# 8_-DAC_and_MIC.net
KiCad netlist of a schematic drawn in Altium Designer
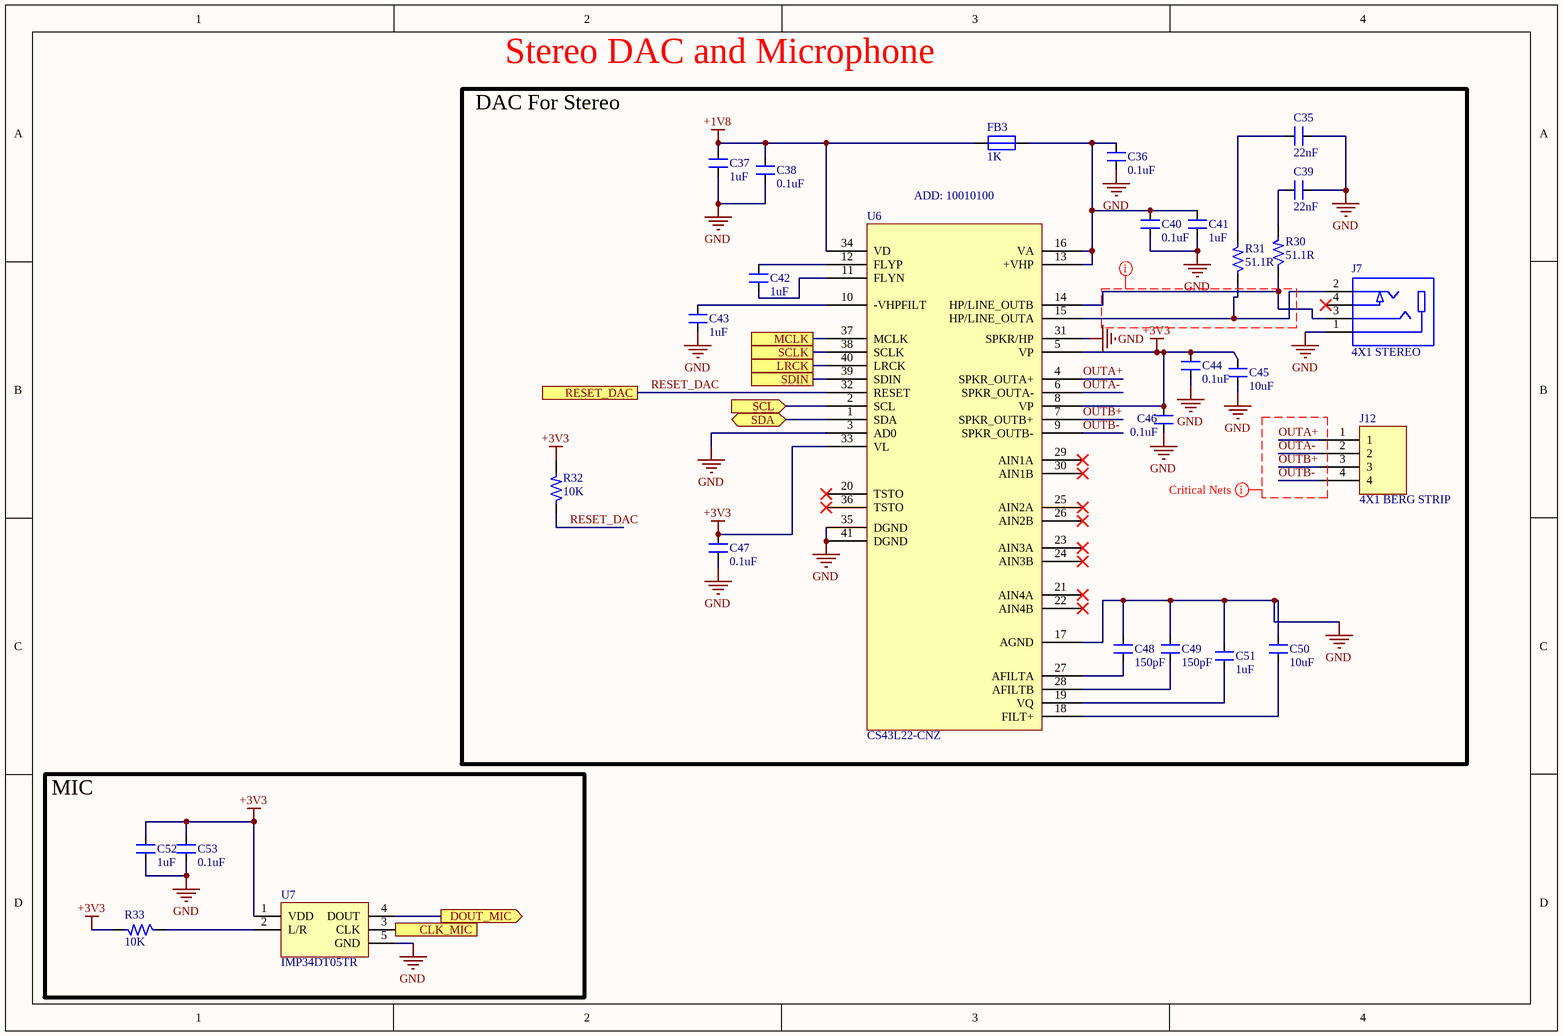
[diagram p0: [8]-DAC and MIC.SchDoc]

(export (version "E")
  (design (tool "Eeschema 10.0.6"))
  (components
    (comp (ref "C35")
      (value "22nF")
      (footprint "CAP_0805")
      (description "0.022µF ±10% 50V Ceramic Capacitor X7R 0805 (2012 Metric)")
      (fields
        (field (name "MANUFACTURER") "Samsung Electro-Mechanics")
        (field (name "MANUFACTURER PART NUMBER") "CL21B223KBANNNC")
      )
      (libsource (lib "ESTEEMPCBLIB") (part "CAP_22nF-50V-10%-0805"))
    )
    (comp (ref "C36")
      (value "0.1uF")
      (footprint "CAP_0805")
      (description "0.1µF ±10% 50V Ceramic Capacitor X7R 0805 (2012 Metric)")
      (fields
        (field (name "MANUFACTURER") "Samsung")
        (field (name "MANUFACTURER PART NUMBER") "CL21B104KBCNNNC")
      )
      (libsource (lib "ESTEEMPCBLIB") (part "CAP_0.1uF-50V-10%-0805"))
    )
    (comp (ref "C37")
      (value "1uF")
      (footprint "CAP_0805")
      (description "1µF ±5% 50V Ceramic Capacitor X7R 0805 (2012 Metric)")
      (fields
        (field (name "MANUFACTURER") "Samsung")
        (field (name "MANUFACTURER PART NUMBER") "CC0805JKX7R9BB105")
      )
      (libsource (lib "ESTEEMPCBLIB") (part "CAP_1uF-50V-5%-0805"))
    )
    (comp (ref "C38")
      (value "0.1uF")
      (footprint "CAP_0805")
      (description "0.1µF ±10% 50V Ceramic Capacitor X7R 0805 (2012 Metric)")
      (fields
        (field (name "MANUFACTURER") "Samsung")
        (field (name "MANUFACTURER PART NUMBER") "CL21B104KBCNNNC")
      )
      (libsource (lib "ESTEEMPCBLIB") (part "CAP_0.1uF-50V-10%-0805"))
    )
    (comp (ref "C39")
      (value "22nF")
      (footprint "CAP_0805")
      (description "0.022µF ±10% 50V Ceramic Capacitor X7R 0805 (2012 Metric)")
      (fields
        (field (name "MANUFACTURER") "Samsung Electro-Mechanics")
        (field (name "MANUFACTURER PART NUMBER") "CL21B223KBANNNC")
      )
      (libsource (lib "ESTEEMPCBLIB") (part "CAP_22nF-50V-10%-0805"))
    )
    (comp (ref "C40")
      (value "0.1uF")
      (footprint "CAP_0805")
      (description "0.1µF ±10% 50V Ceramic Capacitor X7R 0805 (2012 Metric)")
      (fields
        (field (name "MANUFACTURER") "Samsung")
        (field (name "MANUFACTURER PART NUMBER") "CL21B104KBCNNNC")
      )
      (libsource (lib "ESTEEMPCBLIB") (part "CAP_0.1uF-50V-10%-0805"))
    )
    (comp (ref "C41")
      (value "1uF")
      (footprint "CAP_0805")
      (description "1µF ±5% 50V Ceramic Capacitor X7R 0805 (2012 Metric)")
      (fields
        (field (name "MANUFACTURER") "Samsung")
        (field (name "MANUFACTURER PART NUMBER") "CC0805JKX7R9BB105")
      )
      (libsource (lib "ESTEEMPCBLIB") (part "CAP_1uF-50V-5%-0805"))
    )
    (comp (ref "C42")
      (value "1uF")
      (footprint "CAP_0805")
      (description "1µF ±5% 50V Ceramic Capacitor X7R 0805 (2012 Metric)")
      (fields
        (field (name "MANUFACTURER") "Samsung")
        (field (name "MANUFACTURER PART NUMBER") "CC0805JKX7R9BB105")
      )
      (libsource (lib "ESTEEMPCBLIB") (part "CAP_1uF-50V-5%-0805"))
    )
    (comp (ref "C43")
      (value "1uF")
      (footprint "CAP_0805")
      (description "1µF ±5% 50V Ceramic Capacitor X7R 0805 (2012 Metric)")
      (fields
        (field (name "MANUFACTURER") "Samsung")
        (field (name "MANUFACTURER PART NUMBER") "CC0805JKX7R9BB105")
      )
      (libsource (lib "ESTEEMPCBLIB") (part "CAP_1uF-50V-5%-0805"))
    )
    (comp (ref "C44")
      (value "0.1uF")
      (footprint "CAP_0805")
      (description "0.1µF ±10% 50V Ceramic Capacitor X7R 0805 (2012 Metric)")
      (fields
        (field (name "MANUFACTURER") "Samsung")
        (field (name "MANUFACTURER PART NUMBER") "CL21B104KBCNNNC")
      )
      (libsource (lib "ESTEEMPCBLIB") (part "CAP_0.1uF-50V-10%-0805"))
    )
    (comp (ref "C45")
      (value "10uF")
      (footprint "CAP_1206")
      (description "10µF ±10% 50V Ceramic Capacitor X7R 1206 (3216 Metric)")
      (fields
        (field (name "MANUFACTURER") "KEMET")
        (field (name "MANUFACTURER PART NUMBER") "CL31B106KBHNNNE")
      )
      (libsource (lib "ESTEEMPCBLIB") (part "CAP_10uF-50V-10%-1206"))
    )
    (comp (ref "C46")
      (value "0.1uF")
      (footprint "CAP_0805")
      (description "0.1µF ±10% 50V Ceramic Capacitor X7R 0805 (2012 Metric)")
      (fields
        (field (name "MANUFACTURER") "Samsung")
        (field (name "MANUFACTURER PART NUMBER") "CL21B104KBCNNNC")
      )
      (libsource (lib "ESTEEMPCBLIB") (part "CAP_0.1uF-50V-10%-0805"))
    )
    (comp (ref "C47")
      (value "0.1uF")
      (footprint "CAP_0805")
      (description "0.1µF ±10% 50V Ceramic Capacitor X7R 0805 (2012 Metric)")
      (fields
        (field (name "MANUFACTURER") "Samsung")
        (field (name "MANUFACTURER PART NUMBER") "CL21B104KBCNNNC")
      )
      (libsource (lib "ESTEEMPCBLIB") (part "CAP_0.1uF-50V-10%-0805"))
    )
    (comp (ref "C48")
      (value "150pF")
      (footprint "CAP_0805")
      (description "150pF ±10% 50V Ceramic Capacitor C0G, NP0 0805 (2012 Metric)")
      (fields
        (field (name "MANUFACTURER") "AVX Corporation")
        (field (name "MANUFACTURER PART NUMBER") "08055A151KAT2A")
      )
      (libsource (lib "ESTEEMPCBLIB") (part "CAP_150pF-50V-10%-0805"))
    )
    (comp (ref "C49")
      (value "150pF")
      (footprint "CAP_0805")
      (description "150pF ±10% 50V Ceramic Capacitor C0G, NP0 0805 (2012 Metric)")
      (fields
        (field (name "MANUFACTURER") "AVX Corporation")
        (field (name "MANUFACTURER PART NUMBER") "08055A151KAT2A")
      )
      (libsource (lib "ESTEEMPCBLIB") (part "CAP_150pF-50V-10%-0805"))
    )
    (comp (ref "C50")
      (value "10uF")
      (footprint "CAP_1206")
      (description "10µF ±10% 50V Ceramic Capacitor X7R 1206 (3216 Metric)")
      (fields
        (field (name "MANUFACTURER") "KEMET")
        (field (name "MANUFACTURER PART NUMBER") "CL31B106KBHNNNE")
      )
      (libsource (lib "ESTEEMPCBLIB") (part "CAP_10uF-50V-10%-1206"))
    )
    (comp (ref "C51")
      (value "1uF")
      (footprint "CAP_0805")
      (description "1µF ±5% 50V Ceramic Capacitor X7R 0805 (2012 Metric)")
      (fields
        (field (name "MANUFACTURER") "Samsung")
        (field (name "MANUFACTURER PART NUMBER") "CC0805JKX7R9BB105")
      )
      (libsource (lib "ESTEEMPCBLIB") (part "CAP_1uF-50V-5%-0805"))
    )
    (comp (ref "C52")
      (value "1uF")
      (footprint "CAP_0805")
      (description "1µF ±5% 50V Ceramic Capacitor X7R 0805 (2012 Metric)")
      (fields
        (field (name "MANUFACTURER") "Samsung")
        (field (name "MANUFACTURER PART NUMBER") "CC0805JKX7R9BB105")
      )
      (libsource (lib "ESTEEMPCBLIB") (part "CAP_1uF-50V-5%-0805"))
    )
    (comp (ref "C53")
      (value "0.1uF")
      (footprint "CAP_0805")
      (description "0.1µF ±10% 50V Ceramic Capacitor X7R 0805 (2012 Metric)")
      (fields
        (field (name "MANUFACTURER") "Samsung")
        (field (name "MANUFACTURER PART NUMBER") "CL21B104KBCNNNC")
      )
      (libsource (lib "ESTEEMPCBLIB") (part "CAP_0.1uF-50V-10%-0805"))
    )
    (comp (ref "FB3")
      (value "1K")
      (footprint "IND_0805")
      (description "1 kOhms @ 100MHz 1 Power Line Ferrite Bead 0805 (2012 Metric) 1.6A")
      (fields
        (field (name "MANUFACTURER") "Laird")
        (field (name "MANUFACTURER PART NUMBER") "BLM21SP102SH1D")
      )
      (libsource (lib "ESTEEMPCBLIB") (part "FB_1K-100MHZ-1.6A-0805"))
    )
    (comp (ref "J7")
      (value "4X1 STEREO")
      (footprint "CON_SJ-2504A-SMT-TR_SMD")
      (fields
        (field (name "MANUFACTURER") "CUI Devices")
        (field (name "MANUFACTURER PART NUMBER") "SJ-2504A-SMT-TR")
      )
      (libsource (lib "ESTEEMPCBLIB") (part "CON-PLG-STEREO_4X1-100-RA-SMD"))
    )
    (comp (ref "J12")
      (value "4X1 BERG STRIP")
      (footprint "CON4_100_40D72_TH_ST_MALE")
      (description "4 Pins, 1 Row 2.54mm Pitch, Straight bergstrip, Male")
      (fields (field (name "MANUFACTURER") "NA"))
      (libsource (lib "ESTEEMPCBLIB") (part "CON-BS-PLG_4X1-100-ST-TH"))
    )
    (comp (ref "R30")
      (value "51.1R")
      (footprint "RES_0603")
      (description "51.1 Ohms ±1% 0.1W, 1/10W Chip Resistor 0603 (1608 Metric) Thick Film")
      (fields
        (field (name "MANUFACTURER") "Vishay Dale")
        (field (name "MANUFACTURER PART NUMBER") "CRCW060351R1FKEAC")
      )
      (libsource (lib "ESTEEMPCBLIB") (part "RES_51.1R-0.1W-1%-0603"))
    )
    (comp (ref "R31")
      (value "51.1R")
      (footprint "RES_0603")
      (description "51.1 Ohms ±1% 0.1W, 1/10W Chip Resistor 0603 (1608 Metric) Thick Film")
      (fields
        (field (name "MANUFACTURER") "Vishay Dale")
        (field (name "MANUFACTURER PART NUMBER") "CRCW060351R1FKEAC")
      )
      (libsource (lib "ESTEEMPCBLIB") (part "RES_51.1R-0.1W-1%-0603"))
    )
    (comp (ref "R32")
      (value "10K")
      (footprint "RES_0603")
      (description "10 kOhms ±1% 0.1W, 1/10W Chip Resistor 0603 (1608 Metric) Automotive AEC-Q200 Thick Film")
      (fields (field (name "MANUFACTURER") "Walsin") (field (name "MANUFACTURER PART NUMBER") "WR06X1002FTL"))
      (libsource (lib "ESTEEMPCBLIB") (part "RES_10K-0.1W-1%-0603"))
    )
    (comp (ref "R33")
      (value "10K")
      (footprint "RES_0603")
      (description "10 kOhms ±1% 0.1W, 1/10W Chip Resistor 0603 (1608 Metric) Automotive AEC-Q200 Thick Film")
      (fields (field (name "MANUFACTURER") "Walsin") (field (name "MANUFACTURER PART NUMBER") "WR06X1002FTL"))
      (libsource (lib "ESTEEMPCBLIB") (part "RES_10K-0.1W-1%-0603"))
    )
    (comp (ref "U6")
      (value "CS43L22-CNZ")
      (footprint "QFN40_19_284_33X9_SMD")
      (description "Audio D/A Converter ICs Low Power Stereo DAC w/ClassD Spkr Driver")
      (fields (field (name "MANUFACTURER") "Cirrus Logic"))
      (libsource (lib "ESTEEMPCBLIB") (part "IC_CS43L22"))
    )
    (comp (ref "U7")
      (value "IMP34DT05TR")
      (footprint "HCLGA-4_53_137_15X37_SMD")
      (description "MEMS Microphones AUTO & INDUSTRIAL SENSORS")
      (fields (field (name "MANUFACTURER") "STMicroelectronics"))
      (libsource (lib "ESTEEMPCBLIB") (part "IC_IMP34DT05TR"))
    )
  )
  (nets
    (net (code "1") (name "+1V8") (class "Default")
      (node (ref "C37") (pin "2") (pinfunction "2_2") (pintype "passive"))
      (node (ref "C38") (pin "2") (pinfunction "2_2") (pintype "passive"))
      (node (ref "FB3") (pin "1") (pinfunction "1_1") (pintype "passive"))
      (node (ref "U6") (pin "34") (pinfunction "VD_34") (pintype "passive"))
    )
    (net (code "2") (name "+3V3") (class "Default")
      (node (ref "C44") (pin "2") (pinfunction "2_2") (pintype "passive"))
      (node (ref "C45") (pin "2") (pinfunction "2_2") (pintype "passive"))
      (node (ref "C46") (pin "2") (pinfunction "2_2") (pintype "passive"))
      (node (ref "C47") (pin "2") (pinfunction "2_2") (pintype "passive"))
      (node (ref "C52") (pin "2") (pinfunction "2_2") (pintype "passive"))
      (node (ref "C53") (pin "2") (pinfunction "2_2") (pintype "passive"))
      (node (ref "R32") (pin "2") (pinfunction "2_2") (pintype "passive"))
      (node (ref "R33") (pin "2") (pinfunction "2_2") (pintype "passive"))
      (node (ref "U6") (pin "33") (pinfunction "VL_33") (pintype "passive"))
      (node (ref "U6") (pin "5") (pinfunction "VP_5") (pintype "passive"))
      (node (ref "U6") (pin "8") (pinfunction "VP_8") (pintype "passive"))
      (node (ref "U7") (pin "1") (pinfunction "VDD_1") (pintype "passive"))
    )
    (net (code "3") (name "/CLK_MIC") (class "Default")
      (node (ref "U7") (pin "3") (pinfunction "CLK_3") (pintype "passive"))
    )
    (net (code "4") (name "/DOUT_MIC") (class "Default")
      (node (ref "U7") (pin "4") (pinfunction "DOUT_4") (pintype "passive"))
    )
    (net (code "5") (name "/LRCK") (class "Default")
      (node (ref "U6") (pin "40") (pinfunction "LRCK_40") (pintype "passive"))
    )
    (net (code "6") (name "/MCLK") (class "Default")
      (node (ref "U6") (pin "37") (pinfunction "MCLK_37") (pintype "passive"))
    )
    (net (code "7") (name "/OUTA+") (class "Default")
      (node (ref "J12") (pin "1") (pinfunction "1_1") (pintype "passive"))
      (node (ref "U6") (pin "4") (pinfunction "SPKR_OUTA+_4") (pintype "passive"))
    )
    (net (code "8") (name "/OUTA-") (class "Default")
      (node (ref "J12") (pin "2") (pinfunction "2_2") (pintype "passive"))
      (node (ref "U6") (pin "6") (pinfunction "SPKR_OUTA-_6") (pintype "passive"))
    )
    (net (code "9") (name "/OUTB+") (class "Default")
      (node (ref "J12") (pin "3") (pinfunction "3_3") (pintype "passive"))
      (node (ref "U6") (pin "7") (pinfunction "SPKR_OUTB+_7") (pintype "passive"))
    )
    (net (code "10") (name "/OUTB-") (class "Default")
      (node (ref "J12") (pin "4") (pinfunction "4_4") (pintype "passive"))
      (node (ref "U6") (pin "9") (pinfunction "SPKR_OUTB-_9") (pintype "passive"))
    )
    (net (code "11") (name "/RESET_DAC") (class "Default")
      (node (ref "R32") (pin "1") (pinfunction "1_1") (pintype "passive"))
      (node (ref "U6") (pin "32") (pinfunction "RESET_32") (pintype "passive"))
    )
    (net (code "12") (name "/SCL") (class "Default")
      (node (ref "U6") (pin "2") (pinfunction "SCL_2") (pintype "passive"))
    )
    (net (code "13") (name "/SCLK") (class "Default")
      (node (ref "U6") (pin "38") (pinfunction "SCLK_38") (pintype "passive"))
    )
    (net (code "14") (name "/SDA") (class "Default")
      (node (ref "U6") (pin "1") (pinfunction "SDA_1") (pintype "passive"))
    )
    (net (code "15") (name "/SDIN") (class "Default")
      (node (ref "U6") (pin "39") (pinfunction "SDIN_39") (pintype "passive"))
    )
    (net (code "16") (name "GND") (class "Default")
      (node (ref "C35") (pin "2") (pinfunction "2_2") (pintype "passive"))
      (node (ref "C36") (pin "1") (pinfunction "1_1") (pintype "passive"))
      (node (ref "C37") (pin "1") (pinfunction "1_1") (pintype "passive"))
      (node (ref "C38") (pin "1") (pinfunction "1_1") (pintype "passive"))
      (node (ref "C39") (pin "2") (pinfunction "2_2") (pintype "passive"))
      (node (ref "C40") (pin "1") (pinfunction "1_1") (pintype "passive"))
      (node (ref "C41") (pin "1") (pinfunction "1_1") (pintype "passive"))
      (node (ref "C43") (pin "1") (pinfunction "1_1") (pintype "passive"))
      (node (ref "C44") (pin "1") (pinfunction "1_1") (pintype "passive"))
      (node (ref "C45") (pin "1") (pinfunction "1_1") (pintype "passive"))
      (node (ref "C46") (pin "1") (pinfunction "1_1") (pintype "passive"))
      (node (ref "C47") (pin "1") (pinfunction "1_1") (pintype "passive"))
      (node (ref "C48") (pin "2") (pinfunction "2_2") (pintype "passive"))
      (node (ref "C49") (pin "2") (pinfunction "2_2") (pintype "passive"))
      (node (ref "C50") (pin "2") (pinfunction "2_2") (pintype "passive"))
      (node (ref "C51") (pin "2") (pinfunction "2_2") (pintype "passive"))
      (node (ref "C52") (pin "1") (pinfunction "1_1") (pintype "passive"))
      (node (ref "C53") (pin "1") (pinfunction "1_1") (pintype "passive"))
      (node (ref "J7") (pin "1") (pinfunction "1_1") (pintype "passive"))
      (node (ref "U6") (pin "17") (pinfunction "AGND_17") (pintype "passive"))
      (node (ref "U6") (pin "3") (pinfunction "AD0_3") (pintype "passive"))
      (node (ref "U6") (pin "31") (pinfunction "SPKR/HP_31") (pintype "passive"))
      (node (ref "U6") (pin "35") (pinfunction "DGND_35") (pintype "passive"))
      (node (ref "U6") (pin "41") (pinfunction "DGND_41") (pintype "passive"))
      (node (ref "U7") (pin "5") (pinfunction "GND_5") (pintype "passive"))
    )
    (net (code "17") (name "Net-(C35-Pad1)") (class "Default")
      (node (ref "C35") (pin "1") (pinfunction "1_1") (pintype "passive"))
      (node (ref "R31") (pin "2") (pinfunction "2_2") (pintype "passive"))
    )
    (net (code "18") (name "Net-(C39-Pad1)") (class "Default")
      (node (ref "C39") (pin "1") (pinfunction "1_1") (pintype "passive"))
      (node (ref "R30") (pin "2") (pinfunction "2_2") (pintype "passive"))
    )
    (net (code "19") (name "Net-(U6-+VHP)") (class "Default")
      (node (ref "C36") (pin "2") (pinfunction "2_2") (pintype "passive"))
      (node (ref "C40") (pin "2") (pinfunction "2_2") (pintype "passive"))
      (node (ref "C41") (pin "2") (pinfunction "2_2") (pintype "passive"))
      (node (ref "FB3") (pin "2") (pinfunction "2_2") (pintype "passive"))
      (node (ref "U6") (pin "13") (pinfunction "+VHP_13") (pintype "passive"))
      (node (ref "U6") (pin "16") (pinfunction "VA_16") (pintype "passive"))
    )
    (net (code "20") (name "Net-(U6--VHPFILT)") (class "Default")
      (node (ref "C43") (pin "2") (pinfunction "2_2") (pintype "passive"))
      (node (ref "U6") (pin "10") (pinfunction "-VHPFILT_10") (pintype "passive"))
    )
    (net (code "21") (name "Net-(U6-AFILTA)") (class "Default")
      (node (ref "C48") (pin "1") (pinfunction "1_1") (pintype "passive"))
      (node (ref "U6") (pin "27") (pinfunction "AFILTA_27") (pintype "passive"))
    )
    (net (code "22") (name "Net-(U6-AFILTB)") (class "Default")
      (node (ref "C49") (pin "1") (pinfunction "1_1") (pintype "passive"))
      (node (ref "U6") (pin "28") (pinfunction "AFILTB_28") (pintype "passive"))
    )
    (net (code "23") (name "Net-(U6-FILT+)") (class "Default")
      (node (ref "C50") (pin "1") (pinfunction "1_1") (pintype "passive"))
      (node (ref "U6") (pin "18") (pinfunction "FILT+_18") (pintype "passive"))
    )
    (net (code "24") (name "Net-(U6-FLYN)") (class "Default")
      (node (ref "C42") (pin "1") (pinfunction "1_1") (pintype "passive"))
      (node (ref "U6") (pin "11") (pinfunction "FLYN_11") (pintype "passive"))
    )
    (net (code "25") (name "Net-(U6-FLYP)") (class "Default")
      (node (ref "C42") (pin "2") (pinfunction "2_2") (pintype "passive"))
      (node (ref "U6") (pin "12") (pinfunction "FLYP_12") (pintype "passive"))
    )
    (net (code "26") (name "Net-(U6-HP{slash}LINE_OUTA)") (class "Default")
      (node (ref "J7") (pin "2") (pinfunction "2_2") (pintype "passive"))
      (node (ref "R31") (pin "1") (pinfunction "1_1") (pintype "passive"))
      (node (ref "U6") (pin "15") (pinfunction "HP/LINE_OUTA_15") (pintype "passive"))
    )
    (net (code "27") (name "Net-(U6-HP{slash}LINE_OUTB)") (class "Default")
      (node (ref "J7") (pin "3") (pinfunction "3_3") (pintype "passive"))
      (node (ref "R30") (pin "1") (pinfunction "1_1") (pintype "passive"))
      (node (ref "U6") (pin "14") (pinfunction "HP/LINE_OUTB_14") (pintype "passive"))
    )
    (net (code "28") (name "Net-(U6-VQ)") (class "Default")
      (node (ref "C51") (pin "1") (pinfunction "1_1") (pintype "passive"))
      (node (ref "U6") (pin "19") (pinfunction "VQ_19") (pintype "passive"))
    )
    (net (code "29") (name "Net-(U7-L{slash}R)") (class "Default")
      (node (ref "R33") (pin "1") (pinfunction "1_1") (pintype "passive"))
      (node (ref "U7") (pin "2") (pinfunction "L/R_2") (pintype "passive"))
    )
    (net (code "30") (name "unconnected-(J7-Pad4)") (class "Default")
      (node (ref "J7") (pin "4") (pinfunction "4_4") (pintype "passive+no_connect"))
    )
    (net (code "31") (name "unconnected-(U6-AIN1A-Pad29)") (class "Default")
      (node (ref "U6") (pin "29") (pinfunction "AIN1A_29") (pintype "passive+no_connect"))
    )
    (net (code "32") (name "unconnected-(U6-AIN1B-Pad30)") (class "Default")
      (node (ref "U6") (pin "30") (pinfunction "AIN1B_30") (pintype "passive+no_connect"))
    )
    (net (code "33") (name "unconnected-(U6-AIN2A-Pad25)") (class "Default")
      (node (ref "U6") (pin "25") (pinfunction "AIN2A_25") (pintype "passive+no_connect"))
    )
    (net (code "34") (name "unconnected-(U6-AIN2B-Pad26)") (class "Default")
      (node (ref "U6") (pin "26") (pinfunction "AIN2B_26") (pintype "passive+no_connect"))
    )
    (net (code "35") (name "unconnected-(U6-AIN3A-Pad23)") (class "Default")
      (node (ref "U6") (pin "23") (pinfunction "AIN3A_23") (pintype "passive+no_connect"))
    )
    (net (code "36") (name "unconnected-(U6-AIN3B-Pad24)") (class "Default")
      (node (ref "U6") (pin "24") (pinfunction "AIN3B_24") (pintype "passive+no_connect"))
    )
    (net (code "37") (name "unconnected-(U6-AIN4A-Pad21)") (class "Default")
      (node (ref "U6") (pin "21") (pinfunction "AIN4A_21") (pintype "passive+no_connect"))
    )
    (net (code "38") (name "unconnected-(U6-AIN4B-Pad22)") (class "Default")
      (node (ref "U6") (pin "22") (pinfunction "AIN4B_22") (pintype "passive+no_connect"))
    )
    (net (code "39") (name "unconnected-(U6-TSTO-Pad20)") (class "Default")
      (node (ref "U6") (pin "20") (pinfunction "TSTO_20") (pintype "passive+no_connect"))
    )
    (net (code "40") (name "unconnected-(U6-TSTO-Pad36)") (class "Default")
      (node (ref "U6") (pin "36") (pinfunction "TSTO_36") (pintype "passive+no_connect"))
    )
  )
)
